# stable_grid_schmitt_trigger.net
KiCad netlist of a schematic drawn in EAGLE
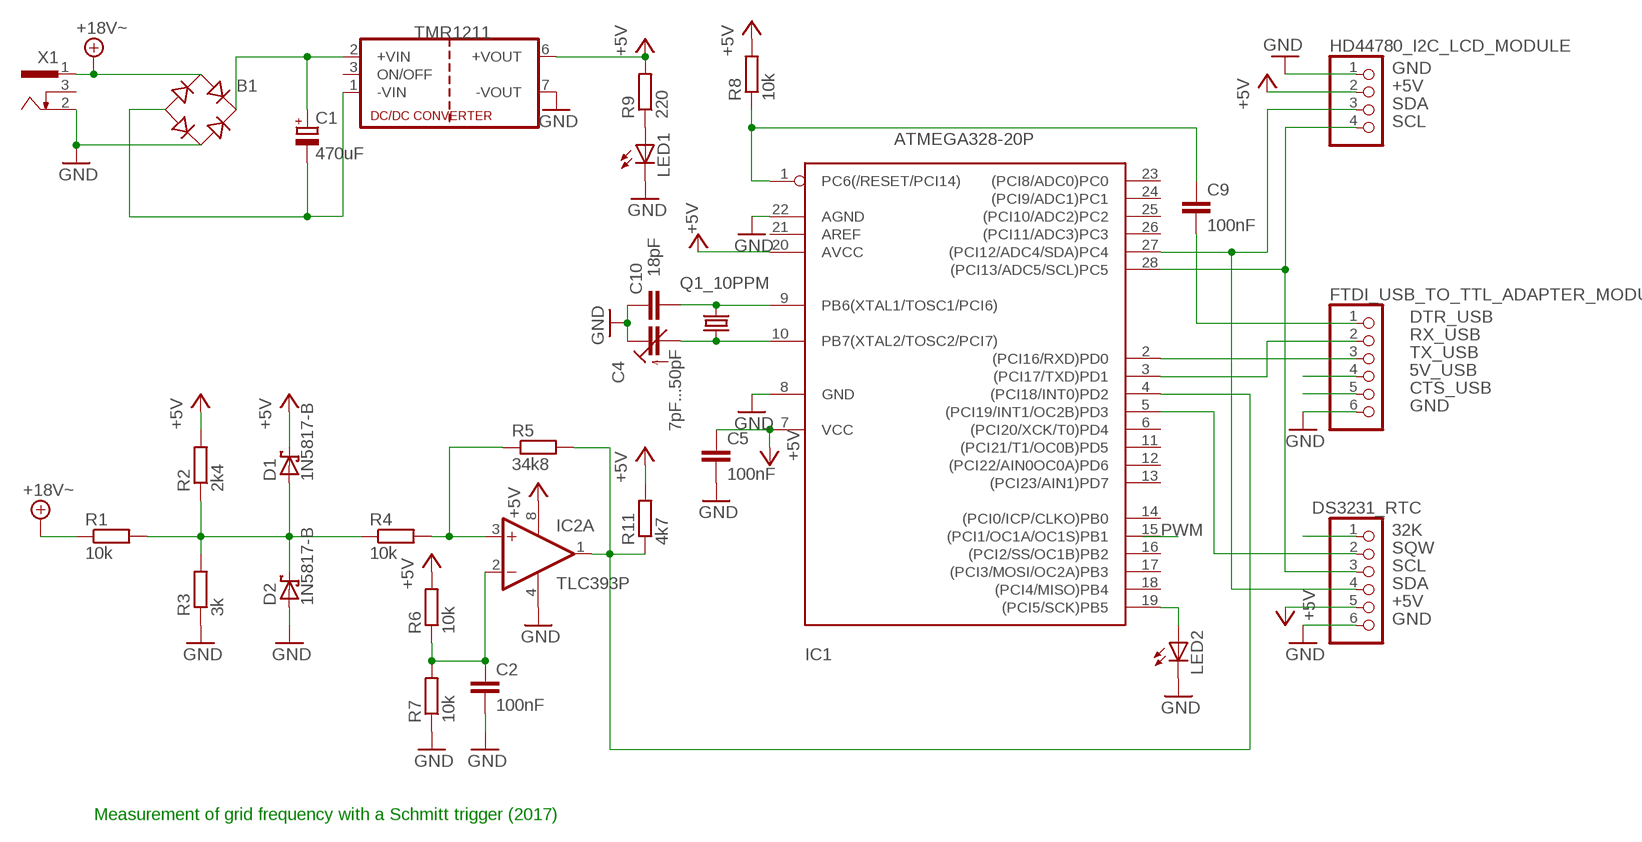
[diagram p0: schematic, sheet 1]

(export (version "E")
  (design (tool "Eeschema 10.0.6"))
  (components
    (comp (ref "B1")
      (value "B-DIL")
      (footprint "eagle-import:B-DIL")
      (libsource (lib "eagle-import") (part "B-DIL"))
    )
    (comp (ref "C1")
      (value "470uF")
      (footprint "eagle-import:085CS_1AR")
      (libsource (lib "eagle-import") (part "CPOL-EU085CS-1AR"))
    )
    (comp (ref "C2")
      (value "100nF")
      (footprint "eagle-import:C025-024X044")
      (libsource (lib "eagle-import") (part "C-EU025-024X044"))
    )
    (comp (ref "C4")
      (value "7pF...50pF")
      (footprint "eagle-import:CTRIM808-BC")
      (libsource (lib "eagle-import") (part "C-TRIMM808"))
    )
    (comp (ref "C5")
      (value "100nF")
      (footprint "eagle-import:C025-024X044")
      (libsource (lib "eagle-import") (part "C-EU025-024X044"))
    )
    (comp (ref "C9")
      (value "100nF")
      (footprint "eagle-import:C025-024X044")
      (libsource (lib "eagle-import") (part "C-EU025-024X044"))
    )
    (comp (ref "C10")
      (value "18pF")
      (footprint "eagle-import:C025-024X044")
      (libsource (lib "eagle-import") (part "C-EU025-024X044"))
    )
    (comp (ref "D1")
      (value "1N5817-B")
      (footprint "eagle-import:DO41-7.6")
      (libsource (lib "eagle-import") (part "1N5817-B"))
    )
    (comp (ref "D2")
      (value "1N5817-B")
      (footprint "eagle-import:DO41-7.6")
      (libsource (lib "eagle-import") (part "1N5817-B"))
    )
    (comp (ref "DS3231_RTC")
      (value "PINHD-1X6")
      (footprint "eagle-import:1X06")
      (libsource (lib "eagle-import") (part "PINHD-1X6"))
    )
    (comp (ref "FTDI_USB_TO_TTL_ADAPTER_MODULE")
      (value "PINHD-1X6")
      (footprint "eagle-import:1X06")
      (libsource (lib "eagle-import") (part "PINHD-1X6"))
    )
    (comp (ref "HD44780_I2C_LCD_MODULE")
      (value "PINHD-1X4")
      (footprint "eagle-import:1X04")
      (libsource (lib "eagle-import") (part "PINHD-1X4"))
    )
    (comp (ref "IC1")
      (value "ATMEGA328-20P")
      (footprint "eagle-import:DIL28-3")
      (libsource (lib "eagle-import") (part "ATMEGA328P-20"))
    )
    (comp (ref "IC2")
      (value "TLC393P")
      (footprint "eagle-import:DIL08")
      (libsource (lib "eagle-import") (part "TLC393P"))
    )
    (comp (ref "LED1")
      (value "LAP4-BOTTOM")
      (footprint "eagle-import:P47F-BOTTOM")
      (libsource (lib "eagle-import") (part "P4-BOTTOMLA"))
    )
    (comp (ref "LED2")
      (value "LAP4-BOTTOM")
      (footprint "eagle-import:P47F-BOTTOM")
      (libsource (lib "eagle-import") (part "P4-BOTTOMLA"))
    )
    (comp (ref "Q1_10PPM")
      (value "CRYSTALHC49S")
      (footprint "eagle-import:HC49_S")
      (libsource (lib "eagle-import") (part "CRYSTALHC49S"))
    )
    (comp (ref "R1")
      (value "10k")
      (footprint "eagle-import:M0805")
      (libsource (lib "eagle-import") (part "R-EU_M0805"))
    )
    (comp (ref "R2")
      (value "2k4")
      (footprint "eagle-import:M0805")
      (libsource (lib "eagle-import") (part "R-EU_M0805"))
    )
    (comp (ref "R3")
      (value "3k")
      (footprint "eagle-import:M0805")
      (libsource (lib "eagle-import") (part "R-EU_M0805"))
    )
    (comp (ref "R4")
      (value "10k")
      (footprint "eagle-import:M0805")
      (libsource (lib "eagle-import") (part "R-EU_M0805"))
    )
    (comp (ref "R5")
      (value "34k8")
      (footprint "eagle-import:M0805")
      (libsource (lib "eagle-import") (part "R-EU_M0805"))
    )
    (comp (ref "R6")
      (value "10k")
      (footprint "eagle-import:M0805")
      (libsource (lib "eagle-import") (part "R-EU_M0805"))
    )
    (comp (ref "R7")
      (value "10k")
      (footprint "eagle-import:M0805")
      (libsource (lib "eagle-import") (part "R-EU_M0805"))
    )
    (comp (ref "R8")
      (value "10k")
      (footprint "eagle-import:M0805")
      (libsource (lib "eagle-import") (part "R-EU_M0805"))
    )
    (comp (ref "R9")
      (value "220")
      (footprint "eagle-import:M0805")
      (libsource (lib "eagle-import") (part "R-EU_M0805"))
    )
    (comp (ref "R11")
      (value "4k7")
      (footprint "eagle-import:M0805")
      (libsource (lib "eagle-import") (part "R-EU_M0805"))
    )
    (comp (ref "SPS1")
      (value "TMR1211")
      (footprint "eagle-import:TRACO_SIP-8")
      (libsource (lib "eagle-import") (part "TMR1211"))
    )
    (comp (ref "X1")
      (value "733980-62")
      (footprint "eagle-import:733980-62")
      (libsource (lib "eagle-import") (part "73398?0-62"))
    )
  )
  (nets
    (net (code "1") (name "+5V") (class "Default")
      (node (ref "C5") (pin "1") (pinfunction "1_1") (pintype "passive"))
      (node (ref "D1") (pin "C") (pinfunction "C_C") (pintype "passive"))
      (node (ref "DS3231_RTC") (pin "5") (pinfunction "5_5") (pintype "passive"))
      (node (ref "HD44780_I2C_LCD_MODULE") (pin "2") (pinfunction "2_2") (pintype "passive"))
      (node (ref "IC1") (pin "20") (pinfunction "AVCC_20") (pintype "bidirectional"))
      (node (ref "IC1") (pin "7") (pinfunction "VCC_7") (pintype "bidirectional"))
      (node (ref "IC2") (pin "8") (pinfunction "V+_8") (pintype "power_in"))
      (node (ref "R11") (pin "2") (pinfunction "2_2") (pintype "passive"))
      (node (ref "R2") (pin "2") (pinfunction "2_2") (pintype "passive"))
      (node (ref "R6") (pin "2") (pinfunction "2_2") (pintype "passive"))
      (node (ref "R8") (pin "2") (pinfunction "2_2") (pintype "passive"))
      (node (ref "R9") (pin "2") (pinfunction "2_2") (pintype "passive"))
      (node (ref "SPS1") (pin "6") (pinfunction "+VOUT_6") (pintype "passive"))
    )
    (net (code "2") (name "+18V~") (class "Default")
      (node (ref "B1") (pin "AC1") (pinfunction "AC1_AC1") (pintype "passive"))
      (node (ref "R1") (pin "1") (pinfunction "1_1") (pintype "passive"))
      (node (ref "X1") (pin "1") (pinfunction "1_1") (pintype "passive"))
    )
    (net (code "3") (name "/5V_USB") (class "Default")
      (node (ref "FTDI_USB_TO_TTL_ADAPTER_MODULE") (pin "4") (pinfunction "4_4") (pintype "passive"))
    )
    (net (code "4") (name "/32K") (class "Default")
      (node (ref "DS3231_RTC") (pin "1") (pinfunction "1_1") (pintype "passive"))
    )
    (net (code "5") (name "/CTS_USB") (class "Default")
      (node (ref "FTDI_USB_TO_TTL_ADAPTER_MODULE") (pin "5") (pinfunction "5_5") (pintype "passive"))
    )
    (net (code "6") (name "/DTR_USB") (class "Default")
      (node (ref "C9") (pin "2") (pinfunction "2_2") (pintype "passive"))
      (node (ref "FTDI_USB_TO_TTL_ADAPTER_MODULE") (pin "1") (pinfunction "1_1") (pintype "passive"))
    )
    (net (code "7") (name "/PWM") (class "Default")
      (node (ref "IC1") (pin "15") (pinfunction "(PCI1/OC1A/OC1S)PB1_15") (pintype "bidirectional"))
    )
    (net (code "8") (name "/RX_USB") (class "Default")
      (node (ref "FTDI_USB_TO_TTL_ADAPTER_MODULE") (pin "2") (pinfunction "2_2") (pintype "passive"))
      (node (ref "IC1") (pin "3") (pinfunction "(PCI17/TXD)PD1_3") (pintype "bidirectional"))
    )
    (net (code "9") (name "/SCL") (class "Default")
      (node (ref "DS3231_RTC") (pin "3") (pinfunction "3_3") (pintype "passive"))
      (node (ref "HD44780_I2C_LCD_MODULE") (pin "4") (pinfunction "4_4") (pintype "passive"))
      (node (ref "IC1") (pin "28") (pinfunction "(PCI13/ADC5/SCL)PC5_28") (pintype "bidirectional"))
    )
    (net (code "10") (name "/SDA") (class "Default")
      (node (ref "DS3231_RTC") (pin "4") (pinfunction "4_4") (pintype "passive"))
      (node (ref "HD44780_I2C_LCD_MODULE") (pin "3") (pinfunction "3_3") (pintype "passive"))
      (node (ref "IC1") (pin "27") (pinfunction "(PCI12/ADC4/SDA)PC4_27") (pintype "bidirectional"))
    )
    (net (code "11") (name "/SQW") (class "Default")
      (node (ref "DS3231_RTC") (pin "2") (pinfunction "2_2") (pintype "passive"))
      (node (ref "IC1") (pin "5") (pinfunction "(PCI19/INT1/OC2B)PD3_5") (pintype "bidirectional"))
    )
    (net (code "12") (name "/TX_USB") (class "Default")
      (node (ref "FTDI_USB_TO_TTL_ADAPTER_MODULE") (pin "3") (pinfunction "3_3") (pintype "passive"))
      (node (ref "IC1") (pin "2") (pinfunction "(PCI16/RXD)PD0_2") (pintype "bidirectional"))
    )
    (net (code "13") (name "GND") (class "Default")
      (node (ref "B1") (pin "AC2") (pinfunction "AC2_AC2") (pintype "passive"))
      (node (ref "C10") (pin "1") (pinfunction "1_1") (pintype "passive"))
      (node (ref "C2") (pin "2") (pinfunction "2_2") (pintype "passive"))
      (node (ref "C4") (pin "1") (pinfunction "E_1") (pintype "passive"))
      (node (ref "C5") (pin "2") (pinfunction "2_2") (pintype "passive"))
      (node (ref "D2") (pin "A") (pinfunction "A_A") (pintype "passive"))
      (node (ref "DS3231_RTC") (pin "6") (pinfunction "6_6") (pintype "passive"))
      (node (ref "FTDI_USB_TO_TTL_ADAPTER_MODULE") (pin "6") (pinfunction "6_6") (pintype "passive"))
      (node (ref "HD44780_I2C_LCD_MODULE") (pin "1") (pinfunction "1_1") (pintype "passive"))
      (node (ref "IC1") (pin "22") (pinfunction "AGND_22") (pintype "bidirectional"))
      (node (ref "IC1") (pin "8") (pinfunction "GND_8") (pintype "bidirectional"))
      (node (ref "IC2") (pin "4") (pinfunction "V-_4") (pintype "power_in"))
      (node (ref "LED1") (pin "C") (pinfunction "C_C") (pintype "passive"))
      (node (ref "LED2") (pin "C") (pinfunction "C_C") (pintype "passive"))
      (node (ref "R3") (pin "1") (pinfunction "1_1") (pintype "passive"))
      (node (ref "R7") (pin "1") (pinfunction "1_1") (pintype "passive"))
      (node (ref "SPS1") (pin "7") (pinfunction "-VOUT_7") (pintype "passive"))
      (node (ref "X1") (pin "2") (pinfunction "2_2") (pintype "passive"))
    )
    (net (code "14") (name "Net-(C4-A)") (class "Default")
      (node (ref "C4") (pin "2") (pinfunction "A_2") (pintype "passive"))
      (node (ref "IC1") (pin "10") (pinfunction "PB7(XTAL2/TOSC2/PCI7)_10") (pintype "bidirectional"))
      (node (ref "Q1_10PPM") (pin "1") (pinfunction "1_1") (pintype "passive"))
    )
    (net (code "15") (name "Net-(D1-PadA)") (class "Default")
      (node (ref "D1") (pin "A") (pinfunction "A_A") (pintype "passive"))
      (node (ref "D2") (pin "C") (pinfunction "C_C") (pintype "passive"))
      (node (ref "R1") (pin "2") (pinfunction "2_2") (pintype "passive"))
      (node (ref "R2") (pin "1") (pinfunction "1_1") (pintype "passive"))
      (node (ref "R3") (pin "2") (pinfunction "2_2") (pintype "passive"))
      (node (ref "R4") (pin "1") (pinfunction "1_1") (pintype "passive"))
    )
    (net (code "16") (name "Net-(IC1-(PCI5{slash}SCK)PB5)") (class "Default")
      (node (ref "IC1") (pin "19") (pinfunction "(PCI5/SCK)PB5_19") (pintype "bidirectional"))
      (node (ref "LED2") (pin "A") (pinfunction "A_A") (pintype "passive"))
    )
    (net (code "17") (name "Net-(IC1-(PCI18{slash}INT0)PD2)") (class "Default")
      (node (ref "IC1") (pin "4") (pinfunction "(PCI18/INT0)PD2_4") (pintype "bidirectional"))
      (node (ref "IC2") (pin "1") (pinfunction "OUT_1") (pintype "output"))
      (node (ref "R11") (pin "1") (pinfunction "1_1") (pintype "passive"))
      (node (ref "R5") (pin "2") (pinfunction "2_2") (pintype "passive"))
    )
    (net (code "18") (name "Net-(IC1-PB6(XTAL1{slash}TOSC1{slash}PCI6))") (class "Default")
      (node (ref "C10") (pin "2") (pinfunction "2_2") (pintype "passive"))
      (node (ref "IC1") (pin "9") (pinfunction "PB6(XTAL1/TOSC1/PCI6)_9") (pintype "bidirectional"))
      (node (ref "Q1_10PPM") (pin "2") (pinfunction "2_2") (pintype "passive"))
    )
    (net (code "19") (name "Net-(IC1-PC6({slash}RESET{slash}PCI14))") (class "Default")
      (node (ref "C9") (pin "1") (pinfunction "1_1") (pintype "passive"))
      (node (ref "IC1") (pin "1") (pinfunction "PC6(/RESET/PCI14)_1") (pintype "bidirectional"))
      (node (ref "R8") (pin "1") (pinfunction "1_1") (pintype "passive"))
    )
    (net (code "20") (name "Net-(IC2A-+IN)") (class "Default")
      (node (ref "IC2") (pin "3") (pinfunction "+IN_3") (pintype "input"))
      (node (ref "R4") (pin "2") (pinfunction "2_2") (pintype "passive"))
      (node (ref "R5") (pin "1") (pinfunction "1_1") (pintype "passive"))
    )
    (net (code "21") (name "Net-(IC2A--IN)") (class "Default")
      (node (ref "C2") (pin "1") (pinfunction "1_1") (pintype "passive"))
      (node (ref "IC2") (pin "2") (pinfunction "-IN_2") (pintype "input"))
      (node (ref "R6") (pin "1") (pinfunction "1_1") (pintype "passive"))
      (node (ref "R7") (pin "2") (pinfunction "2_2") (pintype "passive"))
    )
    (net (code "22") (name "Net-(LED1-PadA)") (class "Default")
      (node (ref "LED1") (pin "A") (pinfunction "A_A") (pintype "passive"))
      (node (ref "R9") (pin "1") (pinfunction "1_1") (pintype "passive"))
    )
    (net (code "23") (name "Net-(SPS1-+VIN)") (class "Default")
      (node (ref "B1") (pin "+") (pinfunction "+_+") (pintype "passive"))
      (node (ref "C1") (pin "+") (pinfunction "+_+") (pintype "passive"))
      (node (ref "SPS1") (pin "2") (pinfunction "+VIN_2") (pintype "power_in"))
    )
    (net (code "24") (name "Net-(SPS1--VIN)") (class "Default")
      (node (ref "B1") (pin "-") (pinfunction "-_-") (pintype "passive"))
      (node (ref "C1") (pin "-") (pinfunction "-_-") (pintype "passive"))
      (node (ref "SPS1") (pin "1") (pinfunction "-VIN_1") (pintype "power_in"))
    )
    (net (code "25") (name "unconnected-(IC1-(PCI0{slash}ICP{slash}CLKO)PB0-Pad14)") (class "Default")
      (node (ref "IC1") (pin "14") (pinfunction "(PCI0/ICP/CLKO)PB0_14") (pintype "bidirectional"))
    )
    (net (code "26") (name "unconnected-(IC1-(PCI2{slash}SS{slash}OC1B)PB2-Pad16)") (class "Default")
      (node (ref "IC1") (pin "16") (pinfunction "(PCI2/SS/OC1B)PB2_16") (pintype "bidirectional"))
    )
    (net (code "27") (name "unconnected-(IC1-(PCI3{slash}MOSI{slash}OC2A)PB3-Pad17)") (class "Default")
      (node (ref "IC1") (pin "17") (pinfunction "(PCI3/MOSI/OC2A)PB3_17") (pintype "bidirectional"))
    )
    (net (code "28") (name "unconnected-(IC1-(PCI4{slash}MISO)PB4-Pad18)") (class "Default")
      (node (ref "IC1") (pin "18") (pinfunction "(PCI4/MISO)PB4_18") (pintype "bidirectional"))
    )
    (net (code "29") (name "unconnected-(IC1-(PCI8{slash}ADC0)PC0-Pad23)") (class "Default")
      (node (ref "IC1") (pin "23") (pinfunction "(PCI8/ADC0)PC0_23") (pintype "bidirectional"))
    )
    (net (code "30") (name "unconnected-(IC1-(PCI9{slash}ADC1)PC1-Pad24)") (class "Default")
      (node (ref "IC1") (pin "24") (pinfunction "(PCI9/ADC1)PC1_24") (pintype "bidirectional"))
    )
    (net (code "31") (name "unconnected-(IC1-(PCI10{slash}ADC2)PC2-Pad25)") (class "Default")
      (node (ref "IC1") (pin "25") (pinfunction "(PCI10/ADC2)PC2_25") (pintype "bidirectional"))
    )
    (net (code "32") (name "unconnected-(IC1-(PCI11{slash}ADC3)PC3-Pad26)") (class "Default")
      (node (ref "IC1") (pin "26") (pinfunction "(PCI11/ADC3)PC3_26") (pintype "bidirectional"))
    )
    (net (code "33") (name "unconnected-(IC1-(PCI20{slash}XCK{slash}T0)PD4-Pad6)") (class "Default")
      (node (ref "IC1") (pin "6") (pinfunction "(PCI20/XCK/T0)PD4_6") (pintype "bidirectional"))
    )
    (net (code "34") (name "unconnected-(IC1-(PCI21{slash}T1{slash}OC0B)PD5-Pad11)") (class "Default")
      (node (ref "IC1") (pin "11") (pinfunction "(PCI21/T1/OC0B)PD5_11") (pintype "bidirectional"))
    )
    (net (code "35") (name "unconnected-(IC1-(PCI22{slash}AIN0OC0A)PD6-Pad12)") (class "Default")
      (node (ref "IC1") (pin "12") (pinfunction "(PCI22/AIN0OC0A)PD6_12") (pintype "bidirectional"))
    )
    (net (code "36") (name "unconnected-(IC1-(PCI23{slash}AIN1)PD7-Pad13)") (class "Default")
      (node (ref "IC1") (pin "13") (pinfunction "(PCI23/AIN1)PD7_13") (pintype "bidirectional"))
    )
    (net (code "37") (name "unconnected-(IC1-AREF-Pad21)") (class "Default")
      (node (ref "IC1") (pin "21") (pinfunction "AREF_21") (pintype "bidirectional"))
    )
    (net (code "38") (name "unconnected-(SPS1-ON{slash}OFF-Pad3)") (class "Default")
      (node (ref "SPS1") (pin "3") (pinfunction "ON/OFF_3") (pintype "passive"))
    )
    (net (code "39") (name "unconnected-(X1-Pad3)") (class "Default")
      (node (ref "X1") (pin "3") (pinfunction "3_3") (pintype "passive"))
    )
  )
)
